# ProPrj_STC8H8K64U__2024-06-28.net
KiCad netlist of a schematic drawn in EasyEDA Pro
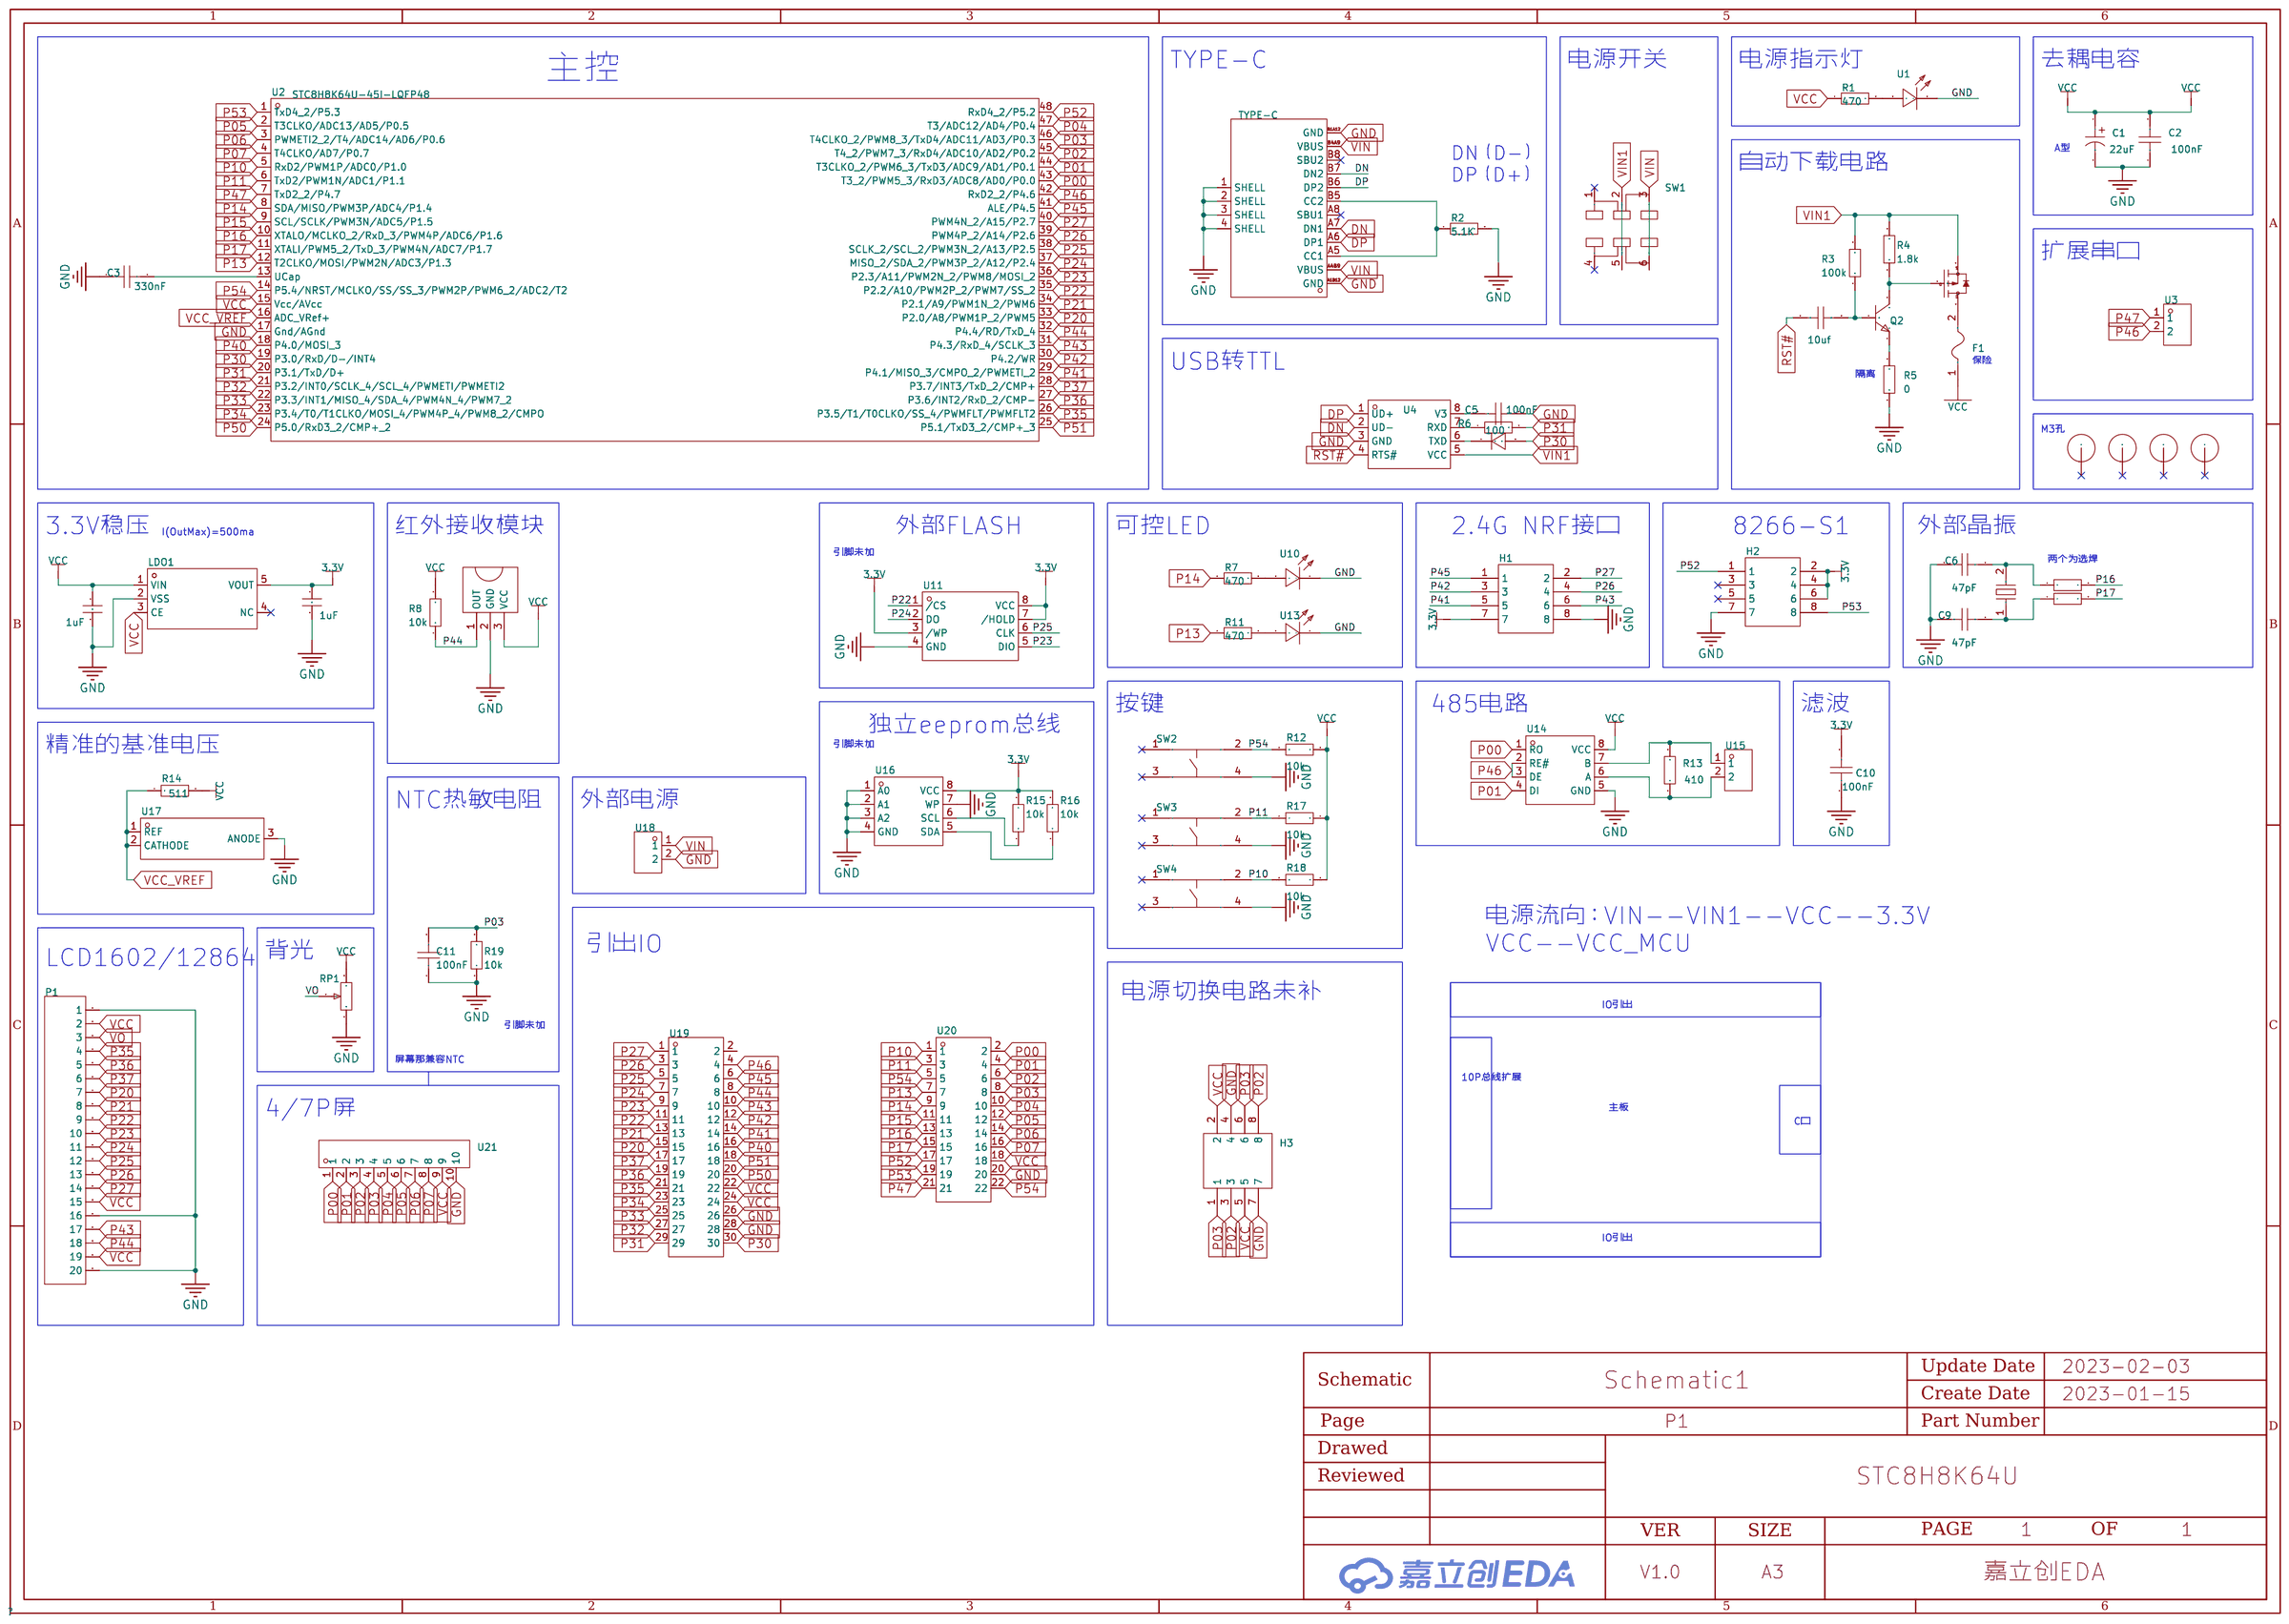
[diagram p0: schematic sheet]

(export (version "E")
  (design (tool "Eeschema 10.0.6"))
  (components
    (comp (ref "C1")
      (value "22uF")
      (footprint "easyedapro:CAP-SMD_L3.2-W1.6")
      (description "容值:22uF;精度:±10%;额定电压:16V;等效串联电阻:6Ω@100kHz;工作温度:-55℃~+125℃;")
      (fields
        (field (name "Manufacturer Part") "CA45-A-16V-22uF-K")
        (field (name "Manufacturer") "CEC(振华新云)")
      )
      (libsource (lib "easyedapro") (part "CA45-A-16V-22UF-K"))
    )
    (comp (ref "C2")
      (value "100nF")
      (footprint "easyedapro:C0603")
      (description "容值:330nF;精度:±5%;额定电压:16V;材质(温度系数):X7R;")
      (fields
        (field (name "Manufacturer Part") "C0603C334J4RAC7867")
        (field (name "Manufacturer") "KEMET(基美)")
      )
      (libsource (lib "easyedapro") (part "C0603C334J4RAC7867"))
    )
    (comp (ref "C3")
      (value "330nF")
      (footprint "easyedapro:C0603")
      (description "容值:330nF;精度:±5%;额定电压:16V;材质(温度系数):X7R;")
      (fields
        (field (name "Manufacturer Part") "C0603C334J4RAC7867")
        (field (name "Manufacturer") "KEMET(基美)")
      )
      (libsource (lib "easyedapro") (part "C0603C334J4RAC7867"))
    )
    (comp (ref "C4")
      (value "10uf")
      (footprint "easyedapro:C0805")
      (libsource (lib "easyedapro") (part "C0805"))
    )
    (comp (ref "C5")
      (value "100nF")
      (footprint "easyedapro:C0603")
      (description "容值:330nF;精度:±5%;额定电压:16V;材质(温度系数):X7R;")
      (fields
        (field (name "Manufacturer Part") "C0603C334J4RAC7867")
        (field (name "Manufacturer") "KEMET(基美)")
      )
      (libsource (lib "easyedapro") (part "C0603C334J4RAC7867"))
    )
    (comp (ref "C6")
      (value "47pF")
      (footprint "easyedapro:C0603")
      (description "容值:330nF;精度:±5%;额定电压:16V;材质(温度系数):X7R;")
      (fields
        (field (name "Manufacturer Part") "C0603C334J4RAC7867")
        (field (name "Manufacturer") "KEMET(基美)")
      )
      (libsource (lib "easyedapro") (part "C0603C334J4RAC7867"))
    )
    (comp (ref "C7")
      (value "1uF")
      (footprint "easyedapro:C0603")
      (description "容值:330nF;精度:±5%;额定电压:16V;材质(温度系数):X7R;")
      (fields
        (field (name "Manufacturer Part") "C0603C334J4RAC7867")
        (field (name "Manufacturer") "KEMET(基美)")
      )
      (libsource (lib "") (part "C0603C334J4RAC7867_1"))
    )
    (comp (ref "C8")
      (value "1uF")
      (footprint "easyedapro:C0603")
      (description "容值:330nF;精度:±5%;额定电压:16V;材质(温度系数):X7R;")
      (fields
        (field (name "Manufacturer Part") "C0603C334J4RAC7867")
        (field (name "Manufacturer") "KEMET(基美)")
      )
      (libsource (lib "") (part "C0603C334J4RAC7867_1"))
    )
    (comp (ref "C9")
      (value "47pF")
      (footprint "easyedapro:C0603")
      (description "容值:330nF;精度:±5%;额定电压:16V;材质(温度系数):X7R;")
      (fields
        (field (name "Manufacturer Part") "C0603C334J4RAC7867")
        (field (name "Manufacturer") "KEMET(基美)")
      )
      (libsource (lib "easyedapro") (part "C0603C334J4RAC7867"))
    )
    (comp (ref "C10")
      (value "100nF")
      (footprint "easyedapro:C0603")
      (description "容值:330nF;精度:±5%;额定电压:16V;材质(温度系数):X7R;")
      (fields
        (field (name "Manufacturer Part") "C0603C334J4RAC7867")
        (field (name "Manufacturer") "KEMET(基美)")
      )
      (libsource (lib "easyedapro") (part "C0603C334J4RAC7867"))
    )
    (comp (ref "C11")
      (value "100nF")
      (footprint "easyedapro:C0603")
      (description "容值:330nF;精度:±5%;额定电压:16V;材质(温度系数):X7R;")
      (fields
        (field (name "Manufacturer Part") "C0603C334J4RAC7867")
        (field (name "Manufacturer") "KEMET(基美)")
      )
      (libsource (lib "easyedapro") (part "C0603C334J4RAC7867"))
    )
    (comp (ref "D1")
      (value "~")
      (footprint "easyedapro:SOD-123_L2.8-W1.8-LS3.7-RD")
      (fields (field (name "Manufacturer Part") "1N4148W-TP") (field (name "Manufacturer") "MCC(美微科)"))
      (libsource (lib "easyedapro") (part "1N4148W-TP"))
    )
    (comp (ref "F1")
      (value "~")
      (footprint "easyedapro:F0805")
      (fields (field (name "Manufacturer Part") "JK-SMD0805-050/6V") (field (name "Manufacturer") "JK(金科)"))
      (libsource (lib "easyedapro") (part "JK-SMD0805-050/6V"))
    )
    (comp (ref "H1")
      (value "A2541WV-2x4P")
      (footprint "easyedapro:HDR-TH_8P-P2.54-V-R2-C4-S2.54_A2541WV-2X4P")
      (fields (field (name "Manufacturer") "CJT(长江连接器)"))
      (libsource (lib "easyedapro") (part "A2541WV-2X4P"))
    )
    (comp (ref "H2")
      (value "A2541WV-2x4P")
      (footprint "easyedapro:HDR-TH_8P-P2.54-V-R2-C4-S2.54_A2541WV-2X4P")
      (fields (field (name "Manufacturer") "CJT(长江连接器)"))
      (libsource (lib "easyedapro") (part "A2541WV-2X4P"))
    )
    (comp (ref "H3")
      (value "A2541WV-2x4P")
      (footprint "easyedapro:HDR-TH_8P-P2.54-V-R2-C4-S2.54_A2541WV-2X4P")
      (fields (field (name "Manufacturer") "CJT(长江连接器)"))
      (libsource (lib "easyedapro") (part "A2541WV-2X4P"))
    )
    (comp (ref "LDO1")
      (value "ME6211C33M5G-N")
      (footprint "easyedapro:SOT-23-5_L3.0-W1.7-P0.95-LS2.8-BR")
      (fields (field (name "Manufacturer") "MICRONE(南京微盟)"))
      (libsource (lib "easyedapro") (part "ME6211C33M5G-N"))
    )
    (comp (ref "P1")
      (value "2.54-1*20P母")
      (footprint "easyedapro:HDR-TH_20P-P2.54-V-F")
      (description "排数:单排;总孔位数:20;间距:2.54mm;插孔结构:1x20P;行距:-;安装类型:直插;塑高:-;触头材质:-;触头镀层:-;")
      (fields (field (name "Manufacturer") "BOOMELE(博穆精密)"))
      (libsource (lib "easyedapro") (part "Header-Female-2.54_1x20"))
    )
    (comp (ref "Q1")
      (value "~")
      (footprint "easyedapro:SOT-23-3_L2.9-W1.3-P0.95-LS2.4-BR")
      (fields (field (name "Manufacturer Part") "AO3401") (field (name "Manufacturer") "KUU"))
      (libsource (lib "easyedapro") (part "AO3401_C2985640"))
    )
    (comp (ref "Q2")
      (value "~")
      (footprint "easyedapro:SS8050-Y1")
      (libsource (lib "easyedapro") (part "SS8050-Y1"))
    )
    (comp (ref "R1")
      (value "470")
      (footprint "easyedapro:R0603")
      (description "阻值:680kΩ;精度:±5%;功率:100mW;温度系数:±100ppm/°C;最大工作电压:75V;工作温度范围:-55°C~+155°C;")
      (fields (field (name "Manufacturer Part") "RC0603JR-07680KL") (field (name "Manufacturer") "YAGEO(国巨)"))
      (libsource (lib "easyedapro") (part "RC0603JR-07680KL"))
    )
    (comp (ref "R2")
      (value "5.1K")
      (footprint "easyedapro:R0603")
      (description "阻值:680kΩ;精度:±5%;功率:100mW;温度系数:±100ppm/°C;最大工作电压:75V;工作温度范围:-55°C~+155°C;")
      (fields (field (name "Manufacturer Part") "RC0603JR-07680KL") (field (name "Manufacturer") "YAGEO(国巨)"))
      (libsource (lib "easyedapro") (part "RC0603JR-07680KL"))
    )
    (comp (ref "R3")
      (value "100k")
      (footprint "easyedapro:R0603")
      (description "阻值:680kΩ;精度:±5%;功率:100mW;温度系数:±100ppm/℃;最大工作电压:75V;工作温度范围:-55℃~+155℃;")
      (fields (field (name "Manufacturer Part") "RC0603JR-07680KL") (field (name "Manufacturer") "YAGEO(国巨)"))
      (libsource (lib "easyedapro") (part "RC0603JR-07680KL"))
    )
    (comp (ref "R4")
      (value "1.8k")
      (footprint "easyedapro:R0603")
      (description "阻值:680kΩ;精度:±5%;功率:100mW;温度系数:±100ppm/℃;最大工作电压:75V;工作温度范围:-55℃~+155℃;")
      (fields (field (name "Manufacturer Part") "RC0603JR-07680KL") (field (name "Manufacturer") "YAGEO(国巨)"))
      (libsource (lib "easyedapro") (part "RC0603JR-07680KL"))
    )
    (comp (ref "R5")
      (value "0")
      (footprint "easyedapro:R0603")
      (description "阻值:680kΩ;精度:±5%;功率:100mW;温度系数:±100ppm/℃;最大工作电压:75V;工作温度范围:-55℃~+155℃;")
      (fields (field (name "Manufacturer Part") "RC0603JR-07680KL") (field (name "Manufacturer") "YAGEO(国巨)"))
      (libsource (lib "easyedapro") (part "RC0603JR-07680KL"))
    )
    (comp (ref "R6")
      (value "100")
      (footprint "easyedapro:R0603")
      (description "阻值:680kΩ;精度:±5%;功率:100mW;温度系数:±100ppm/°C;最大工作电压:75V;工作温度范围:-55°C~+155°C;")
      (fields (field (name "Manufacturer Part") "RC0603JR-07680KL") (field (name "Manufacturer") "YAGEO(国巨)"))
      (libsource (lib "easyedapro") (part "RC0603JR-07680KL"))
    )
    (comp (ref "R7")
      (value "470")
      (footprint "easyedapro:R0603")
      (description "阻值:680kΩ;精度:±5%;功率:100mW;温度系数:±100ppm/°C;最大工作电压:75V;工作温度范围:-55°C~+155°C;")
      (fields (field (name "Manufacturer Part") "RC0603JR-07680KL") (field (name "Manufacturer") "YAGEO(国巨)"))
      (libsource (lib "easyedapro") (part "RC0603JR-07680KL"))
    )
    (comp (ref "R8")
      (value "10k")
      (footprint "easyedapro:R0603")
      (description "阻值:680kΩ;精度:±5%;功率:100mW;温度系数:±100ppm/℃;最大工作电压:75V;工作温度范围:-55℃~+155℃;")
      (fields (field (name "Manufacturer Part") "RC0603JR-07680KL") (field (name "Manufacturer") "YAGEO(国巨)"))
      (libsource (lib "easyedapro") (part "RC0603JR-07680KL"))
    )
    (comp (ref "R9")
      (value "0")
      (footprint "easyedapro:R0603")
      (description "阻值:680kΩ;精度:±5%;功率:100mW;温度系数:±100ppm/°C;最大工作电压:75V;工作温度范围:-55°C~+155°C;")
      (fields (field (name "Manufacturer Part") "RC0603JR-07680KL") (field (name "Manufacturer") "YAGEO(国巨)"))
      (libsource (lib "easyedapro") (part "RC0603JR-07680KL"))
    )
    (comp (ref "R10")
      (value "0")
      (footprint "easyedapro:R0603")
      (description "阻值:680kΩ;精度:±5%;功率:100mW;温度系数:±100ppm/°C;最大工作电压:75V;工作温度范围:-55°C~+155°C;")
      (fields (field (name "Manufacturer Part") "RC0603JR-07680KL") (field (name "Manufacturer") "YAGEO(国巨)"))
      (libsource (lib "easyedapro") (part "RC0603JR-07680KL"))
    )
    (comp (ref "R11")
      (value "470")
      (footprint "easyedapro:R0603")
      (description "阻值:680kΩ;精度:±5%;功率:100mW;温度系数:±100ppm/°C;最大工作电压:75V;工作温度范围:-55°C~+155°C;")
      (fields (field (name "Manufacturer Part") "RC0603JR-07680KL") (field (name "Manufacturer") "YAGEO(国巨)"))
      (libsource (lib "easyedapro") (part "RC0603JR-07680KL"))
    )
    (comp (ref "R12")
      (value "10k")
      (footprint "easyedapro:R0603")
      (description "阻值:680kΩ;精度:±5%;功率:100mW;温度系数:±100ppm/°C;最大工作电压:75V;工作温度范围:-55°C~+155°C;")
      (fields (field (name "Manufacturer Part") "RC0603JR-07680KL") (field (name "Manufacturer") "YAGEO(国巨)"))
      (libsource (lib "easyedapro") (part "RC0603JR-07680KL"))
    )
    (comp (ref "R13")
      (value "410")
      (footprint "easyedapro:R0603")
      (description "阻值:680kΩ;精度:±5%;功率:100mW;温度系数:±100ppm/℃;最大工作电压:75V;工作温度范围:-55℃~+155℃;")
      (fields (field (name "Manufacturer Part") "RC0603JR-07680KL") (field (name "Manufacturer") "YAGEO(国巨)"))
      (libsource (lib "easyedapro") (part "RC0603JR-07680KL"))
    )
    (comp (ref "R14")
      (value "511")
      (footprint "easyedapro:R0603")
      (description "阻值:680kΩ;精度:±5%;功率:100mW;温度系数:±100ppm/°C;最大工作电压:75V;工作温度范围:-55°C~+155°C;")
      (fields (field (name "Manufacturer Part") "RC0603JR-07680KL") (field (name "Manufacturer") "YAGEO(国巨)"))
      (libsource (lib "easyedapro") (part "RC0603JR-07680KL"))
    )
    (comp (ref "R15")
      (value "10k")
      (footprint "easyedapro:R0603")
      (description "阻值:680kΩ;精度:±5%;功率:100mW;温度系数:±100ppm/℃;最大工作电压:75V;工作温度范围:-55℃~+155℃;")
      (fields (field (name "Manufacturer Part") "RC0603JR-07680KL") (field (name "Manufacturer") "YAGEO(国巨)"))
      (libsource (lib "easyedapro") (part "RC0603JR-07680KL"))
    )
    (comp (ref "R16")
      (value "10k")
      (footprint "easyedapro:R0603")
      (description "阻值:680kΩ;精度:±5%;功率:100mW;温度系数:±100ppm/°C;最大工作电压:75V;工作温度范围:-55°C~+155°C;")
      (fields (field (name "Manufacturer Part") "RC0603JR-07680KL") (field (name "Manufacturer") "YAGEO(国巨)"))
      (libsource (lib "easyedapro") (part "RC0603JR-07680KL"))
    )
    (comp (ref "R17")
      (value "10k")
      (footprint "easyedapro:R0603")
      (description "阻值:680kΩ;精度:±5%;功率:100mW;温度系数:±100ppm/°C;最大工作电压:75V;工作温度范围:-55°C~+155°C;")
      (fields (field (name "Manufacturer Part") "RC0603JR-07680KL") (field (name "Manufacturer") "YAGEO(国巨)"))
      (libsource (lib "easyedapro") (part "RC0603JR-07680KL"))
    )
    (comp (ref "R18")
      (value "10k")
      (footprint "easyedapro:R0603")
      (description "阻值:680kΩ;精度:±5%;功率:100mW;温度系数:±100ppm/°C;最大工作电压:75V;工作温度范围:-55°C~+155°C;")
      (fields (field (name "Manufacturer Part") "RC0603JR-07680KL") (field (name "Manufacturer") "YAGEO(国巨)"))
      (libsource (lib "easyedapro") (part "RC0603JR-07680KL"))
    )
    (comp (ref "R19")
      (value "10k")
      (footprint "easyedapro:R0603")
      (description "阻值:680kΩ;精度:±5%;功率:100mW;温度系数:±100ppm/℃;最大工作电压:75V;工作温度范围:-55℃~+155℃;")
      (fields (field (name "Manufacturer Part") "RC0603JR-07680KL") (field (name "Manufacturer") "YAGEO(国巨)"))
      (libsource (lib "easyedapro") (part "RC0603JR-07680KL"))
    )
    (comp (ref "RP1")
      (value "3X3贴片可调电阻10K可调(贴片可调电阻10K3X3EVM3GSX50B1410k±20%松下)")
      (footprint "easyedapro:RES-ADJ-SMD_3P-L3.0-W3.8-P1.75-BR")
      (libsource (lib "easyedapro") (part "3X3贴片可调电阻10K可调(贴片可调电阻10K3X3EVM3GSX50B1410K±20%松下)"))
    )
    (comp (ref "SW1")
      (value "MSK22D18G2 125")
      (footprint "easyedapro:SW-TH_SHOU_MSK22D18G2")
      (description "额定电流(DC):100mA;额定电压(DC):12V;电路结构:双刀双掷;安装方式:卧插;机械寿命:10000;开关颜色:黑色;引脚样式:PC引脚;工作温度:-25~+70;")
      (fields (field (name "Manufacturer") "SHOU HAN(首韩)"))
      (libsource (lib "easyedapro") (part "MSK22D18G2 125"))
    )
    (comp (ref "SW2")
      (value "PTS810SJM250SMTRLFS")
      (footprint "easyedapro:KEY-SMD_4P-L4.2-W3.2-P2.20-LS4.6")
      (description "触点电流:50mA;额定电压(DC):16V;电路结构:单刀单掷;按钮作用方向:顶部触动;致动器样式:圆形按钮;照明颜色:-;开关长度:4.2mm;开关宽度:3.2mm;开关高度:2.5mm;")
      (fields (field (name "Manufacturer") "C&K"))
      (libsource (lib "easyedapro") (part "PTS810SJM250SMTRLFS"))
    )
    (comp (ref "SW3")
      (value "PTS810SJM250SMTRLFS")
      (footprint "easyedapro:KEY-SMD_4P-L4.2-W3.2-P2.20-LS4.6")
      (description "触点电流:50mA;额定电压(DC):16V;电路结构:单刀单掷;按钮作用方向:顶部触动;致动器样式:圆形按钮;照明颜色:-;开关长度:4.2mm;开关宽度:3.2mm;开关高度:2.5mm;")
      (fields (field (name "Manufacturer") "C&K"))
      (libsource (lib "easyedapro") (part "PTS810SJM250SMTRLFS"))
    )
    (comp (ref "SW4")
      (value "PTS810SJM250SMTRLFS")
      (footprint "easyedapro:KEY-SMD_4P-L4.2-W3.2-P2.20-LS4.6")
      (description "触点电流:50mA;额定电压(DC):16V;电路结构:单刀单掷;按钮作用方向:顶部触动;致动器样式:圆形按钮;照明颜色:-;开关长度:4.2mm;开关宽度:3.2mm;开关高度:2.5mm;")
      (fields (field (name "Manufacturer") "C&K"))
      (libsource (lib "easyedapro") (part "PTS810SJM250SMTRLFS"))
    )
    (comp (ref "U1")
      (value "LTE-C9901-GD")
      (footprint "easyedapro:LED0603-RD")
      (libsource (lib "easyedapro") (part "LTE-C9901-GD"))
    )
    (comp (ref "U2")
      (value "STC8H8K64U-45I-LQFP48")
      (footprint "easyedapro:LQFP-48_L7.0-W7.0-P0.50-LS9.0-BL")
      (description "高精准12位ADC")
      (fields (field (name "Manufacturer") "STC(宏晶)"))
      (libsource (lib "easyedapro") (part "STC8H8K64U-45I-LQFP48"))
    )
    (comp (ref "U3")
      (value "XH2.54-WI-2P")
      (footprint "easyedapro:CONN-TH_XH2.54-WI-2P")
      (libsource (lib "easyedapro") (part "XH2.54-WI-2P"))
    )
    (comp (ref "U4")
      (value "~")
      (footprint "easyedapro:SOP-8_L5.0-W4.0-P1.27-LS6.0-BL")
      (fields (field (name "Manufacturer Part") "CH340N") (field (name "Manufacturer") "WCH(南京沁恒)"))
      (libsource (lib "easyedapro") (part "CH340N"))
    )
    (comp (ref "U5") (value "~") (footprint "easyedapro:M3") (libsource (lib "easyedapro") (part "M3")))
    (comp (ref "U6") (value "~") (footprint "easyedapro:M3") (libsource (lib "easyedapro") (part "M3")))
    (comp (ref "U7") (value "~") (footprint "easyedapro:M3") (libsource (lib "easyedapro") (part "M3")))
    (comp (ref "U8") (value "~") (footprint "easyedapro:M3") (libsource (lib "easyedapro") (part "M3")))
    (comp (ref "U9")
      (value "HS0038B")
      (footprint "easyedapro:OPTO-TH_HS0038B-A")
      (libsource (lib "easyedapro") (part "HS0038B"))
    )
    (comp (ref "U10")
      (value "LTE-C9901-GD")
      (footprint "easyedapro:LED0603-RD")
      (libsource (lib "easyedapro") (part "LTE-C9901-GD"))
    )
    (comp (ref "U11")
      (value "W25X16贴片芯片")
      (footprint "easyedapro:SOP-8_L5.3-W5.2-P1.27-LS7.9-BL")
      (libsource (lib "easyedapro") (part "W25X16贴片芯片"))
    )
    (comp (ref "U12")
      (value "32.768K/12.5PF")
      (footprint "easyedapro:CRYSTAL-SMD_L3.2-W1.5-1")
      (libsource (lib "easyedapro") (part "32.768K/12.5PF"))
    )
    (comp (ref "U13")
      (value "LTE-C9901-GD")
      (footprint "easyedapro:LED0603-RD")
      (libsource (lib "easyedapro") (part "LTE-C9901-GD"))
    )
    (comp (ref "U14")
      (value "SP3485EN-L/TR")
      (footprint "easyedapro:SOIC-8_L5.0-W4.0-P1.27-LS6.0-BL")
      (description "类型:收发器;驱动器/接收器:1/1;数据速率:10Mbps;电源电压:3.3V;")
      (fields (field (name "Manufacturer") "MaxLinear"))
      (libsource (lib "easyedapro") (part "SP3485EN-L/TR"))
    )
    (comp (ref "U15")
      (value "XH2.54-WI-2P")
      (footprint "easyedapro:CONN-TH_XH2.54-WI-2P")
      (libsource (lib "easyedapro") (part "XH2.54-WI-2P"))
    )
    (comp (ref "U16")
      (value "24C02")
      (footprint "easyedapro:SOP-8_L4.9-W3.9-P1.27-LS6.0-BL")
      (fields (field (name "Manufacturer") "HX(恒佳兴)"))
      (libsource (lib "easyedapro") (part "24C02"))
    )
    (comp (ref "U17")
      (value "TL431")
      (footprint "easyedapro:SOT-23-3_L2.9-W1.3-P1.90-LS2.4-BR")
      (fields (field (name "Manufacturer") "YFSEMI(江苏佑风微)"))
      (libsource (lib "easyedapro") (part "TL431_C2887585"))
    )
    (comp (ref "U18")
      (value "XH2.54-WI-2P")
      (footprint "easyedapro:CONN-TH_XH2.54-WI-2P")
      (libsource (lib "easyedapro") (part "XH2.54-WI-2P"))
    )
    (comp (ref "U19")
      (value "COM2X15_2.54_DIP")
      (footprint "easyedapro:HDR-TH_30P-P2.54-V-M-R2-C15-S2.54")
      (libsource (lib "easyedapro") (part "COM2X15_2.54_DIP"))
    )
    (comp (ref "U20")
      (value "A2541HWV-2x11P")
      (footprint "easyedapro:HDR-TH_22P-P2.54-V-F-R2-C11-S2.54")
      (fields (field (name "Manufacturer") "CJT(长江连接器)"))
      (libsource (lib "easyedapro") (part "A2541HWV-2X11P_C5340510"))
    )
    (comp (ref "U21")
      (value "cn10_2r54_10x1")
      (footprint "easyedapro:HDR-TH_10P-P2.54-V-F")
      (libsource (lib "easyedapro") (part "CN10_2R54_10X1"))
    )
    (comp (ref "USB1")
      (value "TYPE-C")
      (footprint "easyedapro:USB-C-SMD_TYPE-C16PIN")
      (fields (field (name "Manufacturer Part") "TYPEC12PINCONN"))
      (libsource (lib "easyedapro") (part "TYPEC12PINCONN"))
    )
  )
  (nets
    (net (code "1") (name "3.3V") (class "Default")
      (node (ref "C10") (pin "2") (pinfunction "2_2") (pintype "input"))
      (node (ref "C8") (pin "2") (pinfunction "2_2") (pintype "input"))
      (node (ref "H1") (pin "7") (pinfunction "7_7") (pintype "input"))
      (node (ref "H2") (pin "2") (pinfunction "2_2") (pintype "input"))
      (node (ref "H2") (pin "4") (pinfunction "4_4") (pintype "input"))
      (node (ref "H2") (pin "6") (pinfunction "6_6") (pintype "input"))
      (node (ref "LDO1") (pin "5") (pinfunction "VOUT_5") (pintype "input"))
      (node (ref "R15") (pin "2") (pinfunction "2_2") (pintype "input"))
      (node (ref "R16") (pin "2") (pinfunction "2_2") (pintype "input"))
      (node (ref "U11") (pin "3") (pinfunction "/WP_3") (pintype "input"))
      (node (ref "U11") (pin "7") (pinfunction "/HOLD_7") (pintype "input"))
      (node (ref "U11") (pin "8") (pinfunction "VCC_8") (pintype "input"))
      (node (ref "U16") (pin "8") (pinfunction "VCC_8") (pintype "input"))
    )
    (net (code "2") (name "DN") (class "Default")
      (node (ref "U4") (pin "2") (pinfunction "UD-_2") (pintype "input"))
      (node (ref "USB1") (pin "A7") (pinfunction "DN1_A7") (pintype "input"))
      (node (ref "USB1") (pin "B7") (pinfunction "DN2_B7") (pintype "input"))
    )
    (net (code "3") (name "DP") (class "Default")
      (node (ref "U4") (pin "1") (pinfunction "UD+_1") (pintype "input"))
      (node (ref "USB1") (pin "A6") (pinfunction "DP1_A6") (pintype "input"))
      (node (ref "USB1") (pin "B6") (pinfunction "DP2_B6") (pintype "input"))
    )
    (net (code "4") (name "GND") (class "Default")
      (node (ref "C1") (pin "2") (pinfunction "2_2") (pintype "input"))
      (node (ref "C10") (pin "1") (pinfunction "1_1") (pintype "input"))
      (node (ref "C11") (pin "1") (pinfunction "1_1") (pintype "input"))
      (node (ref "C2") (pin "1") (pinfunction "1_1") (pintype "input"))
      (node (ref "C3") (pin "1") (pinfunction "1_1") (pintype "input"))
      (node (ref "C5") (pin "1") (pinfunction "1_1") (pintype "input"))
      (node (ref "C6") (pin "2") (pinfunction "2_2") (pintype "input"))
      (node (ref "C7") (pin "1") (pinfunction "1_1") (pintype "input"))
      (node (ref "C8") (pin "1") (pinfunction "1_1") (pintype "input"))
      (node (ref "C9") (pin "2") (pinfunction "2_2") (pintype "input"))
      (node (ref "H1") (pin "8") (pinfunction "8_8") (pintype "input"))
      (node (ref "H2") (pin "7") (pinfunction "7_7") (pintype "input"))
      (node (ref "H3") (pin "4") (pinfunction "4_4") (pintype "input"))
      (node (ref "H3") (pin "7") (pinfunction "7_7") (pintype "input"))
      (node (ref "LDO1") (pin "2") (pinfunction "VSS_2") (pintype "input"))
      (node (ref "P1") (pin "1") (pinfunction "1_1") (pintype "input"))
      (node (ref "P1") (pin "16") (pinfunction "16_16") (pintype "input"))
      (node (ref "P1") (pin "20") (pinfunction "20_20") (pintype "input"))
      (node (ref "R19") (pin "1") (pinfunction "1_1") (pintype "input"))
      (node (ref "R2") (pin "2") (pinfunction "2_2") (pintype "input"))
      (node (ref "R5") (pin "1") (pinfunction "1_1") (pintype "input"))
      (node (ref "RP1") (pin "1") (pinfunction "1_1") (pintype "input"))
      (node (ref "SW2") (pin "4") (pinfunction "4_4") (pintype "input"))
      (node (ref "SW3") (pin "4") (pinfunction "4_4") (pintype "input"))
      (node (ref "SW4") (pin "4") (pinfunction "4_4") (pintype "input"))
      (node (ref "U1") (pin "1") (pinfunction "-_1") (pintype "input"))
      (node (ref "U10") (pin "1") (pinfunction "-_1") (pintype "input"))
      (node (ref "U11") (pin "4") (pinfunction "GND_4") (pintype "input"))
      (node (ref "U13") (pin "1") (pinfunction "-_1") (pintype "input"))
      (node (ref "U14") (pin "5") (pinfunction "GND_5") (pintype "input"))
      (node (ref "U16") (pin "1") (pinfunction "A0_1") (pintype "input"))
      (node (ref "U16") (pin "2") (pinfunction "A1_2") (pintype "input"))
      (node (ref "U16") (pin "3") (pinfunction "A2_3") (pintype "input"))
      (node (ref "U16") (pin "4") (pinfunction "GND_4") (pintype "input"))
      (node (ref "U16") (pin "7") (pinfunction "WP_7") (pintype "input"))
      (node (ref "U17") (pin "3") (pinfunction "ANODE_3") (pintype "input"))
      (node (ref "U18") (pin "2") (pinfunction "2_2") (pintype "input"))
      (node (ref "U19") (pin "26") (pinfunction "26_26") (pintype "input"))
      (node (ref "U19") (pin "28") (pinfunction "28_28") (pintype "input"))
      (node (ref "U2") (pin "17") (pinfunction "Gnd/AGnd_17") (pintype "input"))
      (node (ref "U20") (pin "20") (pinfunction "20_20") (pintype "input"))
      (node (ref "U21") (pin "10") (pinfunction "10_10") (pintype "input"))
      (node (ref "U4") (pin "3") (pinfunction "GND_3") (pintype "input"))
      (node (ref "U9") (pin "2") (pinfunction "GND_2") (pintype "input"))
      (node (ref "USB1") (pin "1") (pinfunction "SHELL_1") (pintype "input"))
      (node (ref "USB1") (pin "2") (pinfunction "SHELL_2") (pintype "input"))
      (node (ref "USB1") (pin "3") (pinfunction "SHELL_3") (pintype "input"))
      (node (ref "USB1") (pin "4") (pinfunction "SHELL_4") (pintype "input"))
      (node (ref "USB1") (pin "A1B12") (pinfunction "GND_A1B12") (pintype "input"))
      (node (ref "USB1") (pin "B1A12") (pinfunction "GND_B1A12") (pintype "input"))
    )
    (net (code "5") (name "Net-(C6-Pad1)") (class "Default")
      (node (ref "C6") (pin "1") (pinfunction "1_1") (pintype "input"))
      (node (ref "R9") (pin "1") (pinfunction "1_1") (pintype "input"))
      (node (ref "U12") (pin "2") (pinfunction "2_2") (pintype "input"))
    )
    (net (code "6") (name "Net-(C9-Pad1)") (class "Default")
      (node (ref "C9") (pin "1") (pinfunction "1_1") (pintype "input"))
      (node (ref "R10") (pin "1") (pinfunction "1_1") (pintype "input"))
      (node (ref "U12") (pin "1") (pinfunction "1_1") (pintype "input"))
    )
    (net (code "7") (name "Net-(D1-c)") (class "Default")
      (node (ref "D1") (pin "1") (pinfunction "c_1") (pintype "input"))
      (node (ref "U4") (pin "6") (pinfunction "TXD_6") (pintype "input"))
    )
    (net (code "8") (name "Net-(Q1-D)") (class "Default")
      (node (ref "F1") (pin "2") (pinfunction "2_2") (pintype "input"))
      (node (ref "Q1") (pin "3") (pinfunction "D_3") (pintype "input"))
    )
    (net (code "9") (name "Net-(Q1-G)") (class "Default")
      (node (ref "Q1") (pin "1") (pinfunction "G_1") (pintype "input"))
      (node (ref "Q2") (pin "3") (pinfunction "C_3") (pintype "input"))
      (node (ref "R4") (pin "1") (pinfunction "1_1") (pintype "input"))
    )
    (net (code "10") (name "Net-(Q2-B)") (class "Default")
      (node (ref "C4") (pin "2") (pinfunction "2_2") (pintype "input"))
      (node (ref "Q2") (pin "1") (pinfunction "B_1") (pintype "input"))
      (node (ref "R3") (pin "1") (pinfunction "1_1") (pintype "input"))
    )
    (net (code "11") (name "Net-(Q2-E)") (class "Default")
      (node (ref "Q2") (pin "2") (pinfunction "E_2") (pintype "input"))
      (node (ref "R5") (pin "2") (pinfunction "2_2") (pintype "input"))
    )
    (net (code "12") (name "Net-(U1-+)") (class "Default")
      (node (ref "R1") (pin "2") (pinfunction "2_2") (pintype "input"))
      (node (ref "U1") (pin "2") (pinfunction "+_2") (pintype "input"))
    )
    (net (code "13") (name "Net-(U2-UCap)") (class "Default")
      (node (ref "C3") (pin "2") (pinfunction "2_2") (pintype "input"))
      (node (ref "U2") (pin "13") (pinfunction "UCap_13") (pintype "input"))
    )
    (net (code "14") (name "Net-(U4-RXD)") (class "Default")
      (node (ref "R6") (pin "1") (pinfunction "1_1") (pintype "input"))
      (node (ref "U4") (pin "7") (pinfunction "RXD_7") (pintype "input"))
    )
    (net (code "15") (name "Net-(U4-V3)") (class "Default")
      (node (ref "C5") (pin "2") (pinfunction "2_2") (pintype "input"))
      (node (ref "U4") (pin "8") (pinfunction "V3_8") (pintype "input"))
    )
    (net (code "16") (name "Net-(U10-+)") (class "Default")
      (node (ref "R7") (pin "2") (pinfunction "2_2") (pintype "input"))
      (node (ref "U10") (pin "2") (pinfunction "+_2") (pintype "input"))
    )
    (net (code "17") (name "Net-(U13-+)") (class "Default")
      (node (ref "R11") (pin "2") (pinfunction "2_2") (pintype "input"))
      (node (ref "U13") (pin "2") (pinfunction "+_2") (pintype "input"))
    )
    (net (code "18") (name "Net-(U14-A)") (class "Default")
      (node (ref "R13") (pin "1") (pinfunction "1_1") (pintype "input"))
      (node (ref "U14") (pin "6") (pinfunction "A_6") (pintype "input"))
      (node (ref "U15") (pin "2") (pinfunction "2_2") (pintype "input"))
    )
    (net (code "19") (name "Net-(U14-B)") (class "Default")
      (node (ref "R13") (pin "2") (pinfunction "2_2") (pintype "input"))
      (node (ref "U14") (pin "7") (pinfunction "B_7") (pintype "input"))
      (node (ref "U15") (pin "1") (pinfunction "1_1") (pintype "input"))
    )
    (net (code "20") (name "Net-(U16-SCL)") (class "Default")
      (node (ref "R15") (pin "1") (pinfunction "1_1") (pintype "input"))
      (node (ref "U16") (pin "6") (pinfunction "SCL_6") (pintype "input"))
    )
    (net (code "21") (name "Net-(U16-SDA)") (class "Default")
      (node (ref "R16") (pin "1") (pinfunction "1_1") (pintype "input"))
      (node (ref "U16") (pin "5") (pinfunction "SDA_5") (pintype "input"))
    )
    (net (code "22") (name "Net-(USB1-CC1)") (class "Default")
      (node (ref "R2") (pin "1") (pinfunction "1_1") (pintype "input"))
      (node (ref "USB1") (pin "A5") (pinfunction "CC1_A5") (pintype "input"))
      (node (ref "USB1") (pin "B5") (pinfunction "CC2_B5") (pintype "input"))
    )
    (net (code "23") (name "P00") (class "Default")
      (node (ref "U14") (pin "1") (pinfunction "RO_1") (pintype "input"))
      (node (ref "U2") (pin "43") (pinfunction "T3_2/PWM5_3/RxD3/ADC8/AD0/P0.0_43") (pintype "input"))
      (node (ref "U20") (pin "2") (pinfunction "2_2") (pintype "input"))
      (node (ref "U21") (pin "1") (pinfunction "1_1") (pintype "input"))
    )
    (net (code "24") (name "P01") (class "Default")
      (node (ref "U14") (pin "4") (pinfunction "DI_4") (pintype "input"))
      (node (ref "U2") (pin "44") (pinfunction "T3CLKO_2/PWM6_3/TxD3/ADC9/AD1/P0.1_44") (pintype "input"))
      (node (ref "U20") (pin "4") (pinfunction "4_4") (pintype "input"))
      (node (ref "U21") (pin "2") (pinfunction "2_2") (pintype "input"))
    )
    (net (code "25") (name "P02") (class "Default")
      (node (ref "H3") (pin "3") (pinfunction "3_3") (pintype "input"))
      (node (ref "H3") (pin "8") (pinfunction "8_8") (pintype "input"))
      (node (ref "U2") (pin "45") (pinfunction "T4_2/PWM7_3/RxD4/ADC10/AD2/P0.2_45") (pintype "input"))
      (node (ref "U20") (pin "6") (pinfunction "6_6") (pintype "input"))
      (node (ref "U21") (pin "3") (pinfunction "3_3") (pintype "input"))
    )
    (net (code "26") (name "P03") (class "Default")
      (node (ref "C11") (pin "2") (pinfunction "2_2") (pintype "input"))
      (node (ref "H3") (pin "1") (pinfunction "1_1") (pintype "input"))
      (node (ref "H3") (pin "6") (pinfunction "6_6") (pintype "input"))
      (node (ref "R19") (pin "2") (pinfunction "2_2") (pintype "input"))
      (node (ref "U2") (pin "46") (pinfunction "T4CLKO_2/PWM8_3/TxD4/ADC11/AD3/P0.3_46") (pintype "input"))
      (node (ref "U20") (pin "8") (pinfunction "8_8") (pintype "input"))
      (node (ref "U21") (pin "4") (pinfunction "4_4") (pintype "input"))
    )
    (net (code "27") (name "P04") (class "Default")
      (node (ref "U2") (pin "47") (pinfunction "T3/ADC12/AD4/P0.4_47") (pintype "input"))
      (node (ref "U20") (pin "10") (pinfunction "10_10") (pintype "input"))
      (node (ref "U21") (pin "5") (pinfunction "5_5") (pintype "input"))
    )
    (net (code "28") (name "P05") (class "Default")
      (node (ref "U2") (pin "2") (pinfunction "T3CLKO/ADC13/AD5/P0.5_2") (pintype "input"))
      (node (ref "U20") (pin "12") (pinfunction "12_12") (pintype "input"))
      (node (ref "U21") (pin "6") (pinfunction "6_6") (pintype "input"))
    )
    (net (code "29") (name "P06") (class "Default")
      (node (ref "U2") (pin "3") (pinfunction "PWMETI2_2/T4/ADC14/AD6/P0.6_3") (pintype "input"))
      (node (ref "U20") (pin "14") (pinfunction "14_14") (pintype "input"))
      (node (ref "U21") (pin "7") (pinfunction "7_7") (pintype "input"))
    )
    (net (code "30") (name "P07") (class "Default")
      (node (ref "U2") (pin "4") (pinfunction "T4CLKO/AD7/P0.7_4") (pintype "input"))
      (node (ref "U20") (pin "16") (pinfunction "16_16") (pintype "input"))
      (node (ref "U21") (pin "8") (pinfunction "8_8") (pintype "input"))
    )
    (net (code "31") (name "P10") (class "Default")
      (node (ref "R18") (pin "1") (pinfunction "1_1") (pintype "input"))
      (node (ref "SW4") (pin "2") (pinfunction "2_2") (pintype "input"))
      (node (ref "U2") (pin "5") (pinfunction "RxD2/PWM1P/ADC0/P1.0_5") (pintype "input"))
      (node (ref "U20") (pin "1") (pinfunction "1_1") (pintype "input"))
    )
    (net (code "32") (name "P11") (class "Default")
      (node (ref "R17") (pin "1") (pinfunction "1_1") (pintype "input"))
      (node (ref "SW3") (pin "2") (pinfunction "2_2") (pintype "input"))
      (node (ref "U2") (pin "6") (pinfunction "TxD2/PWM1N/ADC1/P1.1_6") (pintype "input"))
      (node (ref "U20") (pin "3") (pinfunction "3_3") (pintype "input"))
    )
    (net (code "33") (name "P13") (class "Default")
      (node (ref "R11") (pin "1") (pinfunction "1_1") (pintype "input"))
      (node (ref "U2") (pin "12") (pinfunction "T2CLKO/MOSI/PWM2N/ADC3/P1.3_12") (pintype "input"))
      (node (ref "U20") (pin "7") (pinfunction "7_7") (pintype "input"))
    )
    (net (code "34") (name "P14") (class "Default")
      (node (ref "R7") (pin "1") (pinfunction "1_1") (pintype "input"))
      (node (ref "U2") (pin "8") (pinfunction "SDA/MISO/PWM3P/ADC4/P1.4_8") (pintype "input"))
      (node (ref "U20") (pin "9") (pinfunction "9_9") (pintype "input"))
    )
    (net (code "35") (name "P15") (class "Default")
      (node (ref "U2") (pin "9") (pinfunction "SCL/SCLK/PWM3N/ADC5/P1.5_9") (pintype "input"))
      (node (ref "U20") (pin "11") (pinfunction "11_11") (pintype "input"))
    )
    (net (code "36") (name "P16") (class "Default")
      (node (ref "R9") (pin "2") (pinfunction "2_2") (pintype "input"))
      (node (ref "U2") (pin "10") (pinfunction "XTALO/MCLKO_2/RxD_3/PWM4P/ADC6/P1.6_10") (pintype "input"))
      (node (ref "U20") (pin "13") (pinfunction "13_13") (pintype "input"))
    )
    (net (code "37") (name "P17") (class "Default")
      (node (ref "R10") (pin "2") (pinfunction "2_2") (pintype "input"))
      (node (ref "U2") (pin "11") (pinfunction "XTALI/PWM5_2/TxD_3/PWM4N/ADC7/P1.7_11") (pintype "input"))
      (node (ref "U20") (pin "15") (pinfunction "15_15") (pintype "input"))
    )
    (net (code "38") (name "P20") (class "Default")
      (node (ref "P1") (pin "7") (pinfunction "7_7") (pintype "input"))
      (node (ref "U19") (pin "15") (pinfunction "15_15") (pintype "input"))
      (node (ref "U2") (pin "33") (pinfunction "P2.0/A8/PWM1P_2/PWM5_33") (pintype "input"))
    )
    (net (code "39") (name "P21") (class "Default")
      (node (ref "P1") (pin "8") (pinfunction "8_8") (pintype "input"))
      (node (ref "U19") (pin "13") (pinfunction "13_13") (pintype "input"))
      (node (ref "U2") (pin "34") (pinfunction "P2.1/A9/PWM1N_2/PWM6_34") (pintype "input"))
    )
    (net (code "40") (name "P22") (class "Default")
      (node (ref "P1") (pin "9") (pinfunction "9_9") (pintype "input"))
      (node (ref "U11") (pin "1") (pinfunction "/CS_1") (pintype "input"))
      (node (ref "U19") (pin "11") (pinfunction "11_11") (pintype "input"))
      (node (ref "U2") (pin "35") (pinfunction "P2.2/A10/PWM2P_2/PWM7/SS_2_35") (pintype "input"))
    )
    (net (code "41") (name "P23") (class "Default")
      (node (ref "P1") (pin "10") (pinfunction "10_10") (pintype "input"))
      (node (ref "U11") (pin "5") (pinfunction "DIO_5") (pintype "input"))
      (node (ref "U19") (pin "9") (pinfunction "9_9") (pintype "input"))
      (node (ref "U2") (pin "36") (pinfunction "P2.3/A11/PWM2N_2/PWM8/MOSI_2_36") (pintype "input"))
    )
    (net (code "42") (name "P24") (class "Default")
      (node (ref "P1") (pin "11") (pinfunction "11_11") (pintype "input"))
      (node (ref "U11") (pin "2") (pinfunction "DO_2") (pintype "input"))
      (node (ref "U19") (pin "7") (pinfunction "7_7") (pintype "input"))
      (node (ref "U2") (pin "37") (pinfunction "MISO_2/SDA_2/PWM3P_2/A12/P2.4_37") (pintype "input"))
    )
    (net (code "43") (name "P25") (class "Default")
      (node (ref "P1") (pin "12") (pinfunction "12_12") (pintype "input"))
      (node (ref "U11") (pin "6") (pinfunction "CLK_6") (pintype "input"))
      (node (ref "U19") (pin "5") (pinfunction "5_5") (pintype "input"))
      (node (ref "U2") (pin "38") (pinfunction "SCLK_2/SCL_2/PWM3N_2/A13/P2.5_38") (pintype "input"))
    )
    (net (code "44") (name "P26") (class "Default")
      (node (ref "H1") (pin "4") (pinfunction "4_4") (pintype "input"))
      (node (ref "P1") (pin "13") (pinfunction "13_13") (pintype "input"))
      (node (ref "U19") (pin "3") (pinfunction "3_3") (pintype "input"))
      (node (ref "U2") (pin "39") (pinfunction "PWM4P_2/A14/P2.6_39") (pintype "input"))
    )
    (net (code "45") (name "P27") (class "Default")
      (node (ref "H1") (pin "2") (pinfunction "2_2") (pintype "input"))
      (node (ref "P1") (pin "14") (pinfunction "14_14") (pintype "input"))
      (node (ref "U19") (pin "1") (pinfunction "1_1") (pintype "input"))
      (node (ref "U2") (pin "40") (pinfunction "PWM4N_2/A15/P2.7_40") (pintype "input"))
    )
    (net (code "46") (name "P30") (class "Default")
      (node (ref "D1") (pin "2") (pinfunction "A_2") (pintype "input"))
      (node (ref "U19") (pin "30") (pinfunction "30_30") (pintype "input"))
      (node (ref "U2") (pin "19") (pinfunction "P3.0/RxD/D-/INT4_19") (pintype "input"))
    )
    (net (code "47") (name "P31") (class "Default")
      (node (ref "R6") (pin "2") (pinfunction "2_2") (pintype "input"))
      (node (ref "U19") (pin "29") (pinfunction "29_29") (pintype "input"))
      (node (ref "U2") (pin "20") (pinfunction "P3.1/TxD/D+_20") (pintype "input"))
    )
    (net (code "48") (name "P32") (class "Default")
      (node (ref "U19") (pin "27") (pinfunction "27_27") (pintype "input"))
      (node (ref "U2") (pin "21") (pinfunction "P3.2/INT0/SCLK_4/SCL_4/PWMETI/PWMETI2_21") (pintype "input"))
    )
    (net (code "49") (name "P33") (class "Default")
      (node (ref "U19") (pin "25") (pinfunction "25_25") (pintype "input"))
      (node (ref "U2") (pin "22") (pinfunction "P3.3/INT1/MISO_4/SDA_4/PWM4N_4/PWM7_2_22") (pintype "input"))
    )
    (net (code "50") (name "P34") (class "Default")
      (node (ref "U19") (pin "23") (pinfunction "23_23") (pintype "input"))
      (node (ref "U2") (pin "23") (pinfunction "P3.4/T0/T1CLKO/MOSI_4/PWM4P_4/PWM8_2/CMPO_23") (pintype "input"))
    )
    (net (code "51") (name "P35") (class "Default")
      (node (ref "P1") (pin "4") (pinfunction "4_4") (pintype "input"))
      (node (ref "U19") (pin "21") (pinfunction "21_21") (pintype "input"))
      (node (ref "U2") (pin "26") (pinfunction "P3.5/T1/T0CLKO/SS_4/PWMFLT/PWMFLT2_26") (pintype "input"))
    )
    (net (code "52") (name "P36") (class "Default")
      (node (ref "P1") (pin "5") (pinfunction "5_5") (pintype "input"))
      (node (ref "U19") (pin "19") (pinfunction "19_19") (pintype "input"))
      (node (ref "U2") (pin "27") (pinfunction "P3.6/INT2/RxD_2/CMP-_27") (pintype "input"))
    )
    (net (code "53") (name "P37") (class "Default")
      (node (ref "P1") (pin "6") (pinfunction "6_6") (pintype "input"))
      (node (ref "U19") (pin "17") (pinfunction "17_17") (pintype "input"))
      (node (ref "U2") (pin "28") (pinfunction "P3.7/INT3/TxD_2/CMP+_28") (pintype "input"))
    )
    (net (code "54") (name "P40") (class "Default")
      (node (ref "U19") (pin "16") (pinfunction "16_16") (pintype "input"))
      (node (ref "U2") (pin "18") (pinfunction "P4.0/MOSI_3_18") (pintype "input"))
    )
    (net (code "55") (name "P41") (class "Default")
      (node (ref "H1") (pin "5") (pinfunction "5_5") (pintype "input"))
      (node (ref "U19") (pin "14") (pinfunction "14_14") (pintype "input"))
      (node (ref "U2") (pin "29") (pinfunction "P4.1/MISO_3/CMPO_2/PWMETI_2_29") (pintype "input"))
    )
    (net (code "56") (name "P42") (class "Default")
      (node (ref "H1") (pin "3") (pinfunction "3_3") (pintype "input"))
      (node (ref "U19") (pin "12") (pinfunction "12_12") (pintype "input"))
      (node (ref "U2") (pin "30") (pinfunction "P4.2/WR_30") (pintype "input"))
    )
    (net (code "57") (name "P43") (class "Default")
      (node (ref "H1") (pin "6") (pinfunction "6_6") (pintype "input"))
      (node (ref "P1") (pin "17") (pinfunction "17_17") (pintype "input"))
      (node (ref "U19") (pin "10") (pinfunction "10_10") (pintype "input"))
      (node (ref "U2") (pin "31") (pinfunction "P4.3/RxD_4/SCLK_3_31") (pintype "input"))
    )
    (net (code "58") (name "P44") (class "Default")
      (node (ref "P1") (pin "18") (pinfunction "18_18") (pintype "input"))
      (node (ref "R8") (pin "1") (pinfunction "1_1") (pintype "input"))
      (node (ref "U19") (pin "8") (pinfunction "8_8") (pintype "input"))
      (node (ref "U2") (pin "32") (pinfunction "P4.4/RD/TxD_4_32") (pintype "input"))
      (node (ref "U9") (pin "1") (pinfunction "OUT_1") (pintype "input"))
    )
    (net (code "59") (name "P45") (class "Default")
      (node (ref "H1") (pin "1") (pinfunction "1_1") (pintype "input"))
      (node (ref "U19") (pin "6") (pinfunction "6_6") (pintype "input"))
      (node (ref "U2") (pin "41") (pinfunction "ALE/P4.5_41") (pintype "input"))
    )
    (net (code "60") (name "P46") (class "Default")
      (node (ref "U14") (pin "2") (pinfunction "RE#_2") (pintype "input"))
      (node (ref "U14") (pin "3") (pinfunction "DE_3") (pintype "input"))
      (node (ref "U19") (pin "4") (pinfunction "4_4") (pintype "input"))
      (node (ref "U2") (pin "42") (pinfunction "RxD2_2/P4.6_42") (pintype "input"))
      (node (ref "U3") (pin "2") (pinfunction "2_2") (pintype "input"))
    )
    (net (code "61") (name "P47") (class "Default")
      (node (ref "U2") (pin "7") (pinfunction "TxD2_2/P4.7_7") (pintype "input"))
      (node (ref "U20") (pin "21") (pinfunction "21_21") (pintype "input"))
      (node (ref "U3") (pin "1") (pinfunction "1_1") (pintype "input"))
    )
    (net (code "62") (name "P50") (class "Default")
      (node (ref "U19") (pin "20") (pinfunction "20_20") (pintype "input"))
      (node (ref "U2") (pin "24") (pinfunction "P5.0/RxD3_2/CMP+_2_24") (pintype "input"))
    )
    (net (code "63") (name "P51") (class "Default")
      (node (ref "U19") (pin "18") (pinfunction "18_18") (pintype "input"))
      (node (ref "U2") (pin "25") (pinfunction "P5.1/TxD3_2/CMP+_3_25") (pintype "input"))
    )
    (net (code "64") (name "P52") (class "Default")
      (node (ref "H2") (pin "1") (pinfunction "1_1") (pintype "input"))
      (node (ref "U2") (pin "48") (pinfunction "RxD4_2/P5.2_48") (pintype "input"))
      (node (ref "U20") (pin "17") (pinfunction "17_17") (pintype "input"))
    )
    (net (code "65") (name "P53") (class "Default")
      (node (ref "H2") (pin "8") (pinfunction "8_8") (pintype "input"))
      (node (ref "U2") (pin "1") (pinfunction "TxD4_2/P5.3_1") (pintype "input"))
      (node (ref "U20") (pin "19") (pinfunction "19_19") (pintype "input"))
    )
    (net (code "66") (name "P54") (class "Default")
      (node (ref "R12") (pin "1") (pinfunction "1_1") (pintype "input"))
      (node (ref "SW2") (pin "2") (pinfunction "2_2") (pintype "input"))
      (node (ref "U2") (pin "14") (pinfunction "P5.4/NRST/MCLKO/SS/SS_3/PWM2P/PWM6_2/ADC2/T2_14") (pintype "input"))
      (node (ref "U20") (pin "22") (pinfunction "22_22") (pintype "input"))
      (node (ref "U20") (pin "5") (pinfunction "5_5") (pintype "input"))
    )
    (net (code "67") (name "RST#") (class "Default")
      (node (ref "C4") (pin "1") (pinfunction "1_1") (pintype "input"))
      (node (ref "U4") (pin "4") (pinfunction "RTS#_4") (pintype "input"))
    )
    (net (code "68") (name "VCC") (class "Default")
      (node (ref "C1") (pin "1") (pinfunction "1_1") (pintype "input"))
      (node (ref "C2") (pin "2") (pinfunction "2_2") (pintype "input"))
      (node (ref "C7") (pin "2") (pinfunction "2_2") (pintype "input"))
      (node (ref "F1") (pin "1") (pinfunction "1_1") (pintype "input"))
      (node (ref "H3") (pin "2") (pinfunction "2_2") (pintype "input"))
      (node (ref "H3") (pin "5") (pinfunction "5_5") (pintype "input"))
      (node (ref "LDO1") (pin "1") (pinfunction "VIN_1") (pintype "input"))
      (node (ref "LDO1") (pin "3") (pinfunction "CE_3") (pintype "input"))
      (node (ref "P1") (pin "15") (pinfunction "15_15") (pintype "input"))
      (node (ref "P1") (pin "19") (pinfunction "19_19") (pintype "input"))
      (node (ref "P1") (pin "2") (pinfunction "2_2") (pintype "input"))
      (node (ref "R1") (pin "1") (pinfunction "1_1") (pintype "input"))
      (node (ref "R12") (pin "2") (pinfunction "2_2") (pintype "input"))
      (node (ref "R14") (pin "2") (pinfunction "2_2") (pintype "input"))
      (node (ref "R17") (pin "2") (pinfunction "2_2") (pintype "input"))
      (node (ref "R18") (pin "2") (pinfunction "2_2") (pintype "input"))
      (node (ref "R8") (pin "2") (pinfunction "2_2") (pintype "input"))
      (node (ref "RP1") (pin "3") (pinfunction "3_3") (pintype "input"))
      (node (ref "U14") (pin "8") (pinfunction "VCC_8") (pintype "input"))
      (node (ref "U19") (pin "22") (pinfunction "22_22") (pintype "input"))
      (node (ref "U19") (pin "24") (pinfunction "24_24") (pintype "input"))
      (node (ref "U2") (pin "15") (pinfunction "Vcc/AVcc_15") (pintype "input"))
      (node (ref "U20") (pin "18") (pinfunction "18_18") (pintype "input"))
      (node (ref "U21") (pin "9") (pinfunction "9_9") (pintype "input"))
      (node (ref "U9") (pin "3") (pinfunction "VCC_3") (pintype "input"))
    )
    (net (code "69") (name "VCC_VREF") (class "Default")
      (node (ref "R14") (pin "1") (pinfunction "1_1") (pintype "input"))
      (node (ref "U17") (pin "1") (pinfunction "REF_1") (pintype "input"))
      (node (ref "U17") (pin "2") (pinfunction "CATHODE_2") (pintype "input"))
      (node (ref "U2") (pin "16") (pinfunction "ADC_VRef+_16") (pintype "input"))
    )
    (net (code "70") (name "VIN") (class "Default")
      (node (ref "SW1") (pin "3") (pinfunction "3_3") (pintype "input"))
      (node (ref "U18") (pin "1") (pinfunction "1_1") (pintype "input"))
      (node (ref "USB1") (pin "A4B9") (pinfunction "VBUS_A4B9") (pintype "input"))
      (node (ref "USB1") (pin "B4A9") (pinfunction "VBUS_B4A9") (pintype "input"))
    )
    (net (code "71") (name "VIN1") (class "Default")
      (node (ref "Q1") (pin "2") (pinfunction "S_2") (pintype "input"))
      (node (ref "R3") (pin "2") (pinfunction "2_2") (pintype "input"))
      (node (ref "R4") (pin "2") (pinfunction "2_2") (pintype "input"))
      (node (ref "SW1") (pin "2") (pinfunction "2_2") (pintype "input"))
      (node (ref "U4") (pin "5") (pinfunction "VCC_5") (pintype "input"))
    )
    (net (code "72") (name "VO") (class "Default")
      (node (ref "P1") (pin "3") (pinfunction "3_3") (pintype "input"))
      (node (ref "RP1") (pin "2") (pinfunction "2_2") (pintype "input"))
    )
    (net (code "73") (name "unconnected-(H2-Pad3)") (class "Default")
      (node (ref "H2") (pin "3") (pinfunction "3_3") (pintype "input+no_connect"))
    )
    (net (code "74") (name "unconnected-(H2-Pad5)") (class "Default")
      (node (ref "H2") (pin "5") (pinfunction "5_5") (pintype "input+no_connect"))
    )
    (net (code "75") (name "unconnected-(LDO1-NC-Pad4)") (class "Default")
      (node (ref "LDO1") (pin "4") (pinfunction "NC_4") (pintype "input+no_connect"))
    )
    (net (code "76") (name "unconnected-(SW1-Pad1)") (class "Default")
      (node (ref "SW1") (pin "1") (pinfunction "1_1") (pintype "input+no_connect"))
    )
    (net (code "77") (name "unconnected-(SW1-Pad4)") (class "Default")
      (node (ref "SW1") (pin "4") (pinfunction "4_4") (pintype "input+no_connect"))
    )
    (net (code "78") (name "unconnected-(SW1-Pad5)") (class "Default")
      (node (ref "SW1") (pin "5") (pinfunction "5_5") (pintype "input"))
    )
    (net (code "79") (name "unconnected-(SW1-Pad6)") (class "Default")
      (node (ref "SW1") (pin "6") (pinfunction "6_6") (pintype "input"))
    )
    (net (code "80") (name "unconnected-(SW2-Pad1)") (class "Default")
      (node (ref "SW2") (pin "1") (pinfunction "1_1") (pintype "input+no_connect"))
    )
    (net (code "81") (name "unconnected-(SW2-Pad3)") (class "Default")
      (node (ref "SW2") (pin "3") (pinfunction "3_3") (pintype "input+no_connect"))
    )
    (net (code "82") (name "unconnected-(SW3-Pad1)") (class "Default")
      (node (ref "SW3") (pin "1") (pinfunction "1_1") (pintype "input+no_connect"))
    )
    (net (code "83") (name "unconnected-(SW3-Pad3)") (class "Default")
      (node (ref "SW3") (pin "3") (pinfunction "3_3") (pintype "input+no_connect"))
    )
    (net (code "84") (name "unconnected-(SW4-Pad1)") (class "Default")
      (node (ref "SW4") (pin "1") (pinfunction "1_1") (pintype "input+no_connect"))
    )
    (net (code "85") (name "unconnected-(SW4-Pad3)") (class "Default")
      (node (ref "SW4") (pin "3") (pinfunction "3_3") (pintype "input+no_connect"))
    )
    (net (code "86") (name "unconnected-(U5-Pad1)") (class "Default")
      (node (ref "U5") (pin "1") (pinfunction "1_1") (pintype "unspecified+no_connect"))
    )
    (net (code "87") (name "unconnected-(U6-Pad1)") (class "Default")
      (node (ref "U6") (pin "1") (pinfunction "1_1") (pintype "unspecified+no_connect"))
    )
    (net (code "88") (name "unconnected-(U7-Pad1)") (class "Default")
      (node (ref "U7") (pin "1") (pinfunction "1_1") (pintype "unspecified+no_connect"))
    )
    (net (code "89") (name "unconnected-(U8-Pad1)") (class "Default")
      (node (ref "U8") (pin "1") (pinfunction "1_1") (pintype "unspecified+no_connect"))
    )
    (net (code "90") (name "unconnected-(U19-Pad2)") (class "Default")
      (node (ref "U19") (pin "2") (pinfunction "2_2") (pintype "input"))
    )
    (net (code "91") (name "unconnected-(USB1-SBU1-PadA8)") (class "Default")
      (node (ref "USB1") (pin "A8") (pinfunction "SBU1_A8") (pintype "input+no_connect"))
    )
    (net (code "92") (name "unconnected-(USB1-SBU2-PadB8)") (class "Default")
      (node (ref "USB1") (pin "B8") (pinfunction "SBU2_B8") (pintype "input+no_connect"))
    )
  )
)
